# 2_cubesat_bus.net
KiCad netlist of a schematic drawn in Altium Designer
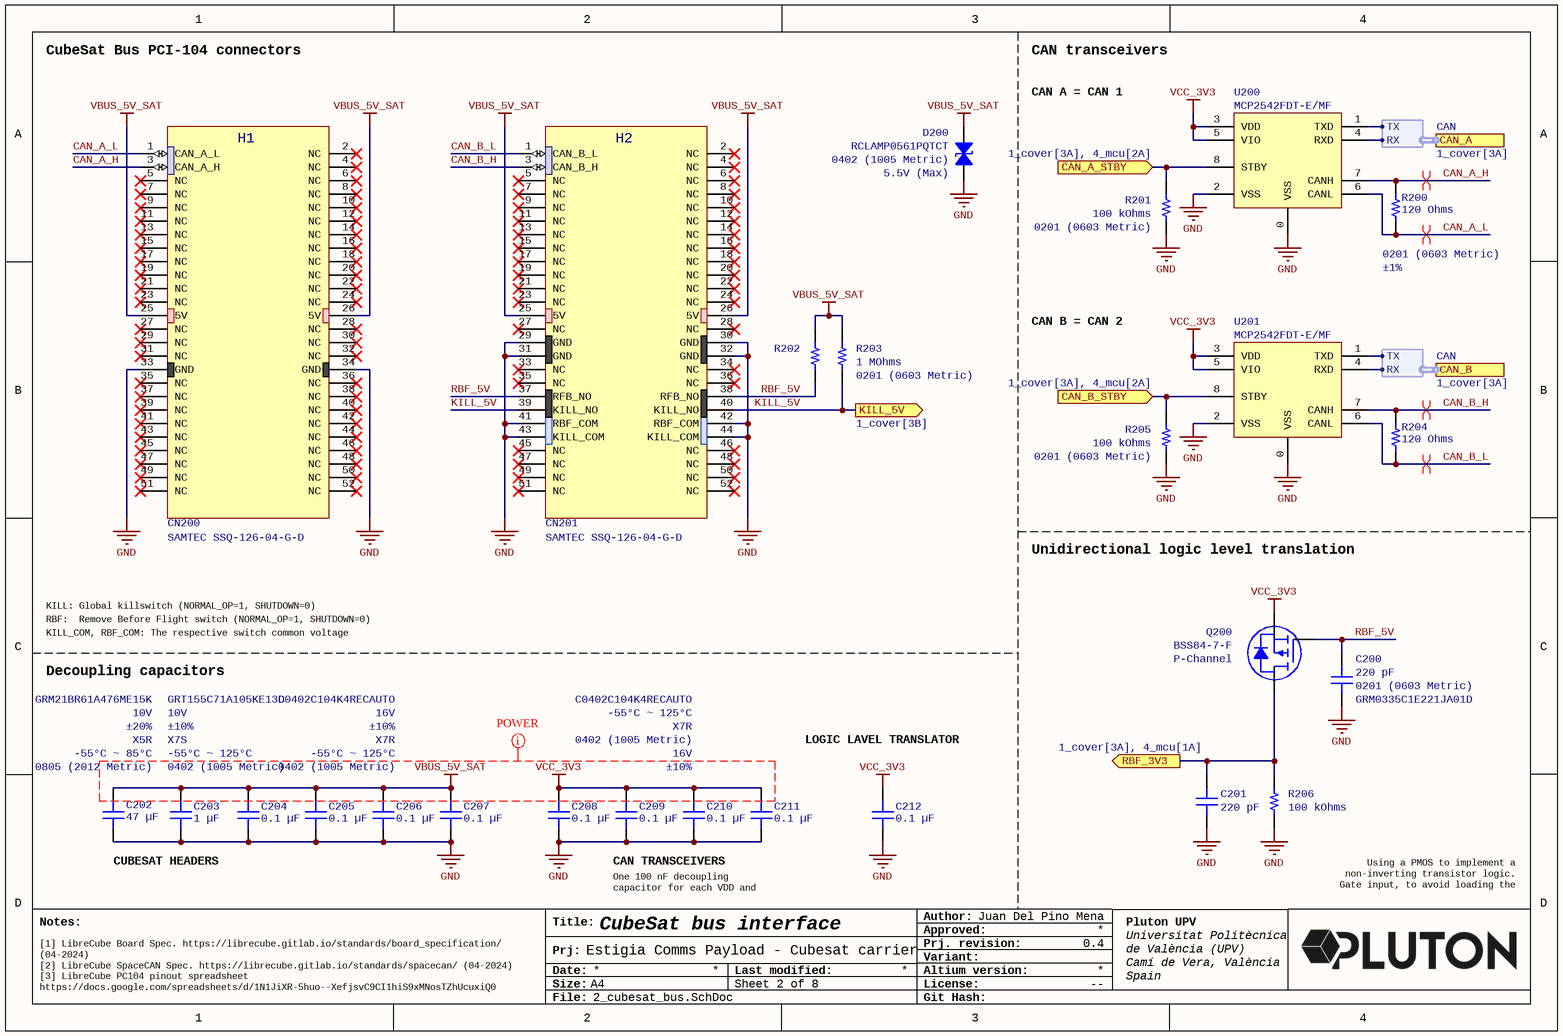
[diagram p0: 2_cubesat_bus.SchDoc]

(export (version "E")
  (design (tool "Eeschema 10.0.6"))
  (components
    (comp (ref "C200")
      (value "220 pF")
      (footprint "CAP 0201_0603")
      (description "CAP CER 220PF 25V C0G/NP0 0201")
      (fields
        (field (name "PART NUMBER") "GRM0335C1E221JA01D")
        (field (name "DEVICE PACKAGE") "0201 (0603 Metric)")
        (field (name "MANUFACTURER") "Murata Electronics")
        (field (name "TOLERANCE") "±5%")
      )
      (libsource (lib "Celestial Altium Library - altium_library") (part "Capacitor"))
    )
    (comp (ref "C201")
      (value "220 pF")
      (footprint "CAP 0201_0603")
      (description "CAP CER 220PF 25V C0G/NP0 0201")
      (fields
        (field (name "PART NUMBER") "GRM0335C1E221JA01D")
        (field (name "MANUFACTURER") "Murata Electronics")
      )
      (libsource (lib "Celestial Altium Library - altium_library") (part "Capacitor"))
    )
    (comp (ref "C202")
      (value "47 µF")
      (footprint "CAP 0805_2012")
      (description "CAP CER 47UF 10V X5R 0805")
      (fields
        (field (name "PART NUMBER") "GRM21BR61A476ME15K")
        (field (name "DEVICE PACKAGE") "0805 (2012 Metric)")
        (field (name "MANUFACTURER") "Murata Electronics")
        (field (name "OPERATING TEMPERATURE") "-55°C ~ 85°C")
        (field (name "TEMPERATURE COEFFICIENT") "X5R")
        (field (name "TOLERANCE") "±20%")
        (field (name "VOLTAGE - RATED") "10V")
      )
      (libsource (lib "Celestial Altium Library - altium_library") (part "Capacitor"))
    )
    (comp (ref "C203")
      (value "1 µF")
      (footprint "CAP 0402_1005")
      (description "CAP CER 1UF 10V X7S 0402")
      (fields
        (field (name "PART NUMBER") "GRT155C71A105KE13D")
        (field (name "DEVICE PACKAGE") "0402 (1005 Metric)")
        (field (name "MANUFACTURER") "Murata Electronics")
        (field (name "OPERATING TEMPERATURE") "-55°C ~ 125°C")
        (field (name "TEMPERATURE COEFFICIENT") "X7S")
        (field (name "TOLERANCE") "±10%")
        (field (name "VOLTAGE - RATED") "10V")
      )
      (libsource (lib "Celestial Altium Library - altium_library") (part "Capacitor"))
    )
    (comp (ref "C204")
      (value "0.1 µF")
      (footprint "CAP 0402_1005")
      (description "CAP CER 0402 0.1UF 16V X7R 10%")
      (fields
        (field (name "PART NUMBER") "C0402C104K4RECAUTO")
        (field (name "MANUFACTURER") "KEMET")
        (field (name "OPERATING TEMPERATURE") "-55°C ~ 125°C")
        (field (name "PACKAGE / CASE") "0402 (1005 Metric)")
        (field (name "TEMPERATURE COEFFICIENT") "X7R")
        (field (name "TOLERANCE") "±10%")
        (field (name "VOLTAGE - RATED") "16V")
      )
      (libsource (lib "Celestial Altium Library - altium_library") (part "Capacitor"))
    )
    (comp (ref "C205")
      (value "0.1 µF")
      (footprint "CAP 0402_1005")
      (description "CAP CER 0402 0.1UF 16V X7R 10%")
      (fields (field (name "PART NUMBER") "C0402C104K4RECAUTO") (field (name "MANUFACTURER") "KEMET"))
      (libsource (lib "Celestial Altium Library - altium_library") (part "Capacitor"))
    )
    (comp (ref "C206")
      (value "0.1 µF")
      (footprint "CAP 0402_1005")
      (description "CAP CER 0402 0.1UF 16V X7R 10%")
      (fields (field (name "PART NUMBER") "C0402C104K4RECAUTO") (field (name "MANUFACTURER") "KEMET"))
      (libsource (lib "Celestial Altium Library - altium_library") (part "Capacitor"))
    )
    (comp (ref "C207")
      (value "0.1 µF")
      (footprint "CAP 0402_1005")
      (description "CAP CER 0402 0.1UF 16V X7R 10%")
      (fields (field (name "PART NUMBER") "C0402C104K4RECAUTO") (field (name "MANUFACTURER") "KEMET"))
      (libsource (lib "Celestial Altium Library - altium_library") (part "Capacitor"))
    )
    (comp (ref "C208")
      (value "0.1 µF")
      (footprint "CAP 0402_1005")
      (description "CAP CER 0402 0.1UF 16V X7R 10%")
      (fields (field (name "PART NUMBER") "C0402C104K4RECAUTO") (field (name "MANUFACTURER") "KEMET"))
      (libsource (lib "Celestial Altium Library - altium_library") (part "Capacitor"))
    )
    (comp (ref "C209")
      (value "0.1 µF")
      (footprint "CAP 0402_1005")
      (description "CAP CER 0402 0.1UF 16V X7R 10%")
      (fields
        (field (name "PART NUMBER") "C0402C104K4RECAUTO")
        (field (name "MANUFACTURER") "KEMET")
        (field (name "OPERATING TEMPERATURE") "-55°C ~ 125°C")
        (field (name "PACKAGE / CASE") "0402 (1005 Metric)")
        (field (name "TEMPERATURE COEFFICIENT") "X7R")
        (field (name "TOLERANCE") "±10%")
        (field (name "VOLTAGE - RATED") "16V")
      )
      (libsource (lib "Celestial Altium Library - altium_library") (part "Capacitor"))
    )
    (comp (ref "C210")
      (value "0.1 µF")
      (footprint "CAP 0402_1005")
      (description "CAP CER 0402 0.1UF 16V X7R 10%")
      (fields (field (name "PART NUMBER") "C0402C104K4RECAUTO") (field (name "MANUFACTURER") "KEMET"))
      (libsource (lib "Celestial Altium Library - altium_library") (part "Capacitor"))
    )
    (comp (ref "C211")
      (value "0.1 µF")
      (footprint "CAP 0402_1005")
      (description "CAP CER 0402 0.1UF 16V X7R 10%")
      (fields (field (name "PART NUMBER") "C0402C104K4RECAUTO") (field (name "MANUFACTURER") "KEMET"))
      (libsource (lib "Celestial Altium Library - altium_library") (part "Capacitor"))
    )
    (comp (ref "C212")
      (value "0.1 µF")
      (footprint "CAP 0402_1005")
      (description "CAP CER 0402 0.1UF 16V X7R 10%")
      (fields (field (name "PART NUMBER") "C0402C104K4RECAUTO") (field (name "MANUFACTURER") "KEMET"))
      (libsource (lib "Celestial Altium Library - altium_library") (part "Capacitor"))
    )
    (comp (ref "CN200")
      (value "SAMTEC SSQ-126-04-G-D")
      (footprint "connectors:SAMTEC SSQ-126-04-G-D")
      (description "LoRa Payload only pins SAMTEC SSQ-126-04-G-D")
      (libsource (lib "cubesat_bus") (part "CubeSat Header H1 LoRa PL"))
    )
    (comp (ref "CN201")
      (value "SAMTEC SSQ-126-04-G-D")
      (footprint "connectors:SAMTEC SSQ-126-04-G-D")
      (description "LoRa Payload only pins")
      (libsource (lib "cubesat_bus") (part "CubeSat Header H2 LoRa PL"))
    )
    (comp (ref "D200")
      (value "RCLAMP0561PQTCT")
      (footprint "0402")
      (description "1-LINE 5V 0.15PF 1.1R ESD SLP100")
      (fields
        (field (name "PART NUMBER") "RCLAMP0561PQTCT")
        (field (name "DEVICE PACKAGE") "0402 (1005 Metric)")
        (field (name "MANUFACTURER") "Semtech Corporation")
        (field (name "VOLTAGE - REVERSE STANDOFF (TYP)") "5.5V (Max)")
      )
      (libsource (lib "Celestial Altium Library - altium_library") (part "Diode TVS"))
    )
    (comp (ref "Q200")
      (value "BSS84-7-F")
      (footprint "DIODES SOT-23-3")
      (description "MOSFET P-CH 50V 130MA SOT23-3")
      (fields
        (field (name "PART NUMBER") "BSS84-7-F")
        (field (name "FET TYPE") "P-Channel")
        (field (name "MANUFACTURER") "Diodes Incorporated")
      )
      (libsource (lib "Celestial Altium Library - altium_library") (part "DIODES MOSFET P-CH SOT-23-3"))
    )
    (comp (ref "R200")
      (value "120 Ohms")
      (footprint "RES 0201_0603")
      (description "RES SMD 120 OHM 1% 1/20W 0201")
      (fields
        (field (name "PART NUMBER") "CRCW0201120RFNED")
        (field (name "DEVICE PACKAGE") "0201 (0603 Metric)")
        (field (name "MANUFACTURER") "Vishay Dale")
        (field (name "TOLERANCE") "±1%")
      )
      (libsource (lib "Celestial Altium Library - altium_library") (part "Resistor"))
    )
    (comp (ref "R201")
      (value "100 kOhms")
      (footprint "RES 0201_0603")
      (description "RES 100K OHM 1% 1/20W 0201")
      (fields
        (field (name "PART NUMBER") "RC0201FR-13100KL")
        (field (name "DEVICE PACKAGE") "0201 (0603 Metric)")
        (field (name "MANUFACTURER") "Yageo")
      )
      (libsource (lib "Celestial Altium Library - altium_library") (part "Resistor"))
    )
    (comp (ref "R202")
      (value "1 MOhms")
      (footprint "RES 0201_0603")
      (description "RES SMD 1M OHM 5% 1/20W 0201")
      (fields (field (name "PART NUMBER") "CRCW02011M00JNED") (field (name "MANUFACTURER") "Vishay Dale"))
      (libsource (lib "Celestial Altium Library - altium_library") (part "Resistor"))
    )
    (comp (ref "R203")
      (value "1 MOhms")
      (footprint "RES 0201_0603")
      (description "RES SMD 1M OHM 5% 1/20W 0201")
      (fields
        (field (name "PART NUMBER") "CRCW02011M00JNED")
        (field (name "DEVICE PACKAGE") "0201 (0603 Metric)")
        (field (name "MANUFACTURER") "Vishay Dale")
      )
      (libsource (lib "Celestial Altium Library - altium_library") (part "Resistor"))
    )
    (comp (ref "R204")
      (value "120 Ohms")
      (footprint "RES 0201_0603")
      (description "RES SMD 120 OHM 1% 1/20W 0201")
      (fields (field (name "PART NUMBER") "CRCW0201120RFNED") (field (name "MANUFACTURER") "Vishay Dale"))
      (libsource (lib "Celestial Altium Library - altium_library") (part "Resistor"))
    )
    (comp (ref "R205")
      (value "100 kOhms")
      (footprint "RES 0201_0603")
      (description "RES 100K OHM 1% 1/20W 0201")
      (fields
        (field (name "PART NUMBER") "RC0201FR-13100KL")
        (field (name "DEVICE PACKAGE") "0201 (0603 Metric)")
        (field (name "MANUFACTURER") "Yageo")
      )
      (libsource (lib "Celestial Altium Library - altium_library") (part "Resistor"))
    )
    (comp (ref "R206")
      (value "100 kOhms")
      (footprint "RES 0201_0603")
      (description "RES 100K OHM 1% 1/20W 0201")
      (fields (field (name "PART NUMBER") "RC0201FR-13100KL") (field (name "MANUFACTURER") "Yageo"))
      (libsource (lib "Celestial Altium Library - altium_library") (part "Resistor"))
    )
    (comp (ref "U200")
      (value "MCP2542FDT-E/MF")
      (footprint "ics:DFN-8 3x3mm")
      (description "IC TRANSCEIVER 1/1 8DFN")
      (fields
        (field (name "MANUFACTURER") "Microchip Technology")
        (field (name "PART NUMBER") "MCP2542FDT-E/MF")
      )
      (libsource (lib "logic") (part "CAN MCP2542FDT-E/MF"))
    )
    (comp (ref "U201")
      (value "MCP2542FDT-E/MF")
      (footprint "ics:DFN-8 3x3mm")
      (description "IC TRANSCEIVER 1/1 8DFN")
      (fields
        (field (name "MANUFACTURER") "Microchip Technology")
        (field (name "PART NUMBER") "MCP2542FDT-E/MF")
      )
      (libsource (lib "logic") (part "CAN MCP2542FDT-E/MF"))
    )
  )
  (nets
    (net (code "2") (name "/CAN_A_H") (class "Default")
      (node (ref "CN200") (pin "3") (pinfunction "CAN_A_H_3") (pintype "bidirectional"))
      (node (ref "R200") (pin "2") (pinfunction "2_2") (pintype "passive"))
      (node (ref "U200") (pin "7") (pinfunction "CANH_7") (pintype "passive"))
    )
    (net (code "3") (name "/CAN_A_L") (class "Default")
      (node (ref "CN200") (pin "1") (pinfunction "CAN_A_L_1") (pintype "bidirectional"))
      (node (ref "R200") (pin "1") (pinfunction "1_1") (pintype "passive"))
      (node (ref "U200") (pin "6") (pinfunction "CANL_6") (pintype "passive"))
    )
    (net (code "4") (name "/CAN_A_STBY") (class "Default")
      (node (ref "R201") (pin "2") (pinfunction "2_2") (pintype "passive"))
      (node (ref "U200") (pin "8") (pinfunction "STBY_8") (pintype "passive"))
    )
    (net (code "5") (name "/CAN_B_H") (class "Default")
      (node (ref "CN201") (pin "3") (pinfunction "CAN_B_H_3") (pintype "bidirectional"))
      (node (ref "R204") (pin "2") (pinfunction "2_2") (pintype "passive"))
      (node (ref "U201") (pin "7") (pinfunction "CANH_7") (pintype "passive"))
    )
    (net (code "6") (name "/CAN_B_L") (class "Default")
      (node (ref "CN201") (pin "1") (pinfunction "CAN_B_L_1") (pintype "bidirectional"))
      (node (ref "R204") (pin "1") (pinfunction "1_1") (pintype "passive"))
      (node (ref "U201") (pin "6") (pinfunction "CANL_6") (pintype "passive"))
    )
    (net (code "7") (name "/CAN_B_STBY") (class "Default")
      (node (ref "R205") (pin "2") (pinfunction "2_2") (pintype "passive"))
      (node (ref "U201") (pin "8") (pinfunction "STBY_8") (pintype "passive"))
    )
    (net (code "8") (name "/KILL_5V") (class "Default")
      (node (ref "CN201") (pin "39") (pinfunction "KILL_NO_39") (pintype "passive"))
      (node (ref "CN201") (pin "40") (pinfunction "KILL_NO_40") (pintype "passive"))
      (node (ref "R203") (pin "1") (pinfunction "1_1") (pintype "passive"))
    )
    (net (code "9") (name "/RBF_3V3") (class "Default")
      (node (ref "C201") (pin "2") (pinfunction "2_2") (pintype "passive"))
      (node (ref "Q200") (pin "3") (pinfunction "D_3") (pintype "passive"))
      (node (ref "R206") (pin "1") (pinfunction "1_1") (pintype "passive"))
    )
    (net (code "10") (name "/RBF_5V") (class "Default")
      (node (ref "C200") (pin "2") (pinfunction "2_2") (pintype "passive"))
      (node (ref "CN201") (pin "37") (pinfunction "RFB_NO_37") (pintype "passive"))
      (node (ref "CN201") (pin "38") (pinfunction "RFB_NO_38") (pintype "passive"))
      (node (ref "Q200") (pin "1") (pinfunction "G_1") (pintype "passive"))
      (node (ref "R202") (pin "1") (pinfunction "1_1") (pintype "passive"))
    )
    (net (code "12") (name "GND") (class "Default")
      (node (ref "C200") (pin "1") (pinfunction "1_1") (pintype "passive"))
      (node (ref "C201") (pin "1") (pinfunction "1_1") (pintype "passive"))
      (node (ref "C202") (pin "1") (pinfunction "1_1") (pintype "passive"))
      (node (ref "C203") (pin "1") (pinfunction "1_1") (pintype "passive"))
      (node (ref "C204") (pin "1") (pinfunction "1_1") (pintype "passive"))
      (node (ref "C205") (pin "1") (pinfunction "1_1") (pintype "passive"))
      (node (ref "C206") (pin "1") (pinfunction "1_1") (pintype "passive"))
      (node (ref "C207") (pin "1") (pinfunction "1_1") (pintype "passive"))
      (node (ref "C208") (pin "1") (pinfunction "1_1") (pintype "passive"))
      (node (ref "C209") (pin "1") (pinfunction "1_1") (pintype "passive"))
      (node (ref "C210") (pin "1") (pinfunction "1_1") (pintype "passive"))
      (node (ref "C211") (pin "1") (pinfunction "1_1") (pintype "passive"))
      (node (ref "C212") (pin "1") (pinfunction "1_1") (pintype "passive"))
      (node (ref "CN200") (pin "33") (pinfunction "GND_33") (pintype "power_in"))
      (node (ref "CN200") (pin "34") (pinfunction "GND_34") (pintype "power_in"))
      (node (ref "CN201") (pin "29") (pinfunction "GND_29") (pintype "power_in"))
      (node (ref "CN201") (pin "30") (pinfunction "GND_30") (pintype "power_in"))
      (node (ref "CN201") (pin "31") (pinfunction "GND_31") (pintype "power_in"))
      (node (ref "CN201") (pin "32") (pinfunction "GND_32") (pintype "power_in"))
      (node (ref "CN201") (pin "41") (pinfunction "RBF_COM_41") (pintype "passive"))
      (node (ref "CN201") (pin "42") (pinfunction "RBF_COM_42") (pintype "passive"))
      (node (ref "CN201") (pin "43") (pinfunction "KILL_COM_43") (pintype "passive"))
      (node (ref "CN201") (pin "44") (pinfunction "KILL_COM_44") (pintype "passive"))
      (node (ref "D200") (pin "1") (pinfunction "1_1") (pintype "passive"))
      (node (ref "R201") (pin "1") (pinfunction "1_1") (pintype "passive"))
      (node (ref "R205") (pin "1") (pinfunction "1_1") (pintype "passive"))
      (node (ref "R206") (pin "2") (pinfunction "2_2") (pintype "passive"))
      (node (ref "U200") (pin "0") (pinfunction "VSS_0") (pintype "passive"))
      (node (ref "U200") (pin "2") (pinfunction "VSS_2") (pintype "passive"))
      (node (ref "U201") (pin "0") (pinfunction "VSS_0") (pintype "passive"))
      (node (ref "U201") (pin "2") (pinfunction "VSS_2") (pintype "passive"))
    )
    (net (code "13") (name "VBUS_5V_SAT") (class "Default")
      (node (ref "C202") (pin "2") (pinfunction "2_2") (pintype "passive"))
      (node (ref "C203") (pin "2") (pinfunction "2_2") (pintype "passive"))
      (node (ref "C204") (pin "2") (pinfunction "2_2") (pintype "passive"))
      (node (ref "C205") (pin "2") (pinfunction "2_2") (pintype "passive"))
      (node (ref "C206") (pin "2") (pinfunction "2_2") (pintype "passive"))
      (node (ref "C207") (pin "2") (pinfunction "2_2") (pintype "passive"))
      (node (ref "CN200") (pin "25") (pinfunction "5V_25") (pintype "power_in"))
      (node (ref "CN200") (pin "26") (pinfunction "5V_26") (pintype "power_in"))
      (node (ref "CN201") (pin "25") (pinfunction "5V_25") (pintype "power_in"))
      (node (ref "CN201") (pin "26") (pinfunction "5V_26") (pintype "power_in"))
      (node (ref "D200") (pin "2") (pinfunction "2_2") (pintype "passive"))
      (node (ref "R202") (pin "2") (pinfunction "2_2") (pintype "passive"))
      (node (ref "R203") (pin "2") (pinfunction "2_2") (pintype "passive"))
    )
    (net (code "14") (name "VCC_3V3") (class "Default")
      (node (ref "C208") (pin "2") (pinfunction "2_2") (pintype "passive"))
      (node (ref "C209") (pin "2") (pinfunction "2_2") (pintype "passive"))
      (node (ref "C210") (pin "2") (pinfunction "2_2") (pintype "passive"))
      (node (ref "C211") (pin "2") (pinfunction "2_2") (pintype "passive"))
      (node (ref "C212") (pin "2") (pinfunction "2_2") (pintype "passive"))
      (node (ref "Q200") (pin "2") (pinfunction "S_2") (pintype "passive"))
      (node (ref "U200") (pin "3") (pinfunction "VDD_3") (pintype "passive"))
      (node (ref "U200") (pin "5") (pinfunction "VIO_5") (pintype "passive"))
      (node (ref "U201") (pin "3") (pinfunction "VDD_3") (pintype "passive"))
      (node (ref "U201") (pin "5") (pinfunction "VIO_5") (pintype "passive"))
    )
    (net (code "15") (name "unconnected-(CN200-NC-Pad2)") (class "Default")
      (node (ref "CN200") (pin "2") (pinfunction "NC_2") (pintype "passive+no_connect"))
    )
    (net (code "16") (name "unconnected-(CN200-NC-Pad4)") (class "Default")
      (node (ref "CN200") (pin "4") (pinfunction "NC_4") (pintype "passive+no_connect"))
    )
    (net (code "17") (name "unconnected-(CN200-NC-Pad5)") (class "Default")
      (node (ref "CN200") (pin "5") (pinfunction "NC_5") (pintype "passive+no_connect"))
    )
    (net (code "18") (name "unconnected-(CN200-NC-Pad6)") (class "Default")
      (node (ref "CN200") (pin "6") (pinfunction "NC_6") (pintype "passive+no_connect"))
    )
    (net (code "19") (name "unconnected-(CN200-NC-Pad7)") (class "Default")
      (node (ref "CN200") (pin "7") (pinfunction "NC_7") (pintype "passive+no_connect"))
    )
    (net (code "20") (name "unconnected-(CN200-NC-Pad8)") (class "Default")
      (node (ref "CN200") (pin "8") (pinfunction "NC_8") (pintype "passive+no_connect"))
    )
    (net (code "21") (name "unconnected-(CN200-NC-Pad9)") (class "Default")
      (node (ref "CN200") (pin "9") (pinfunction "NC_9") (pintype "passive+no_connect"))
    )
    (net (code "22") (name "unconnected-(CN200-NC-Pad10)") (class "Default")
      (node (ref "CN200") (pin "10") (pinfunction "NC_10") (pintype "passive+no_connect"))
    )
    (net (code "23") (name "unconnected-(CN200-NC-Pad11)") (class "Default")
      (node (ref "CN200") (pin "11") (pinfunction "NC_11") (pintype "passive+no_connect"))
    )
    (net (code "24") (name "unconnected-(CN200-NC-Pad12)") (class "Default")
      (node (ref "CN200") (pin "12") (pinfunction "NC_12") (pintype "passive+no_connect"))
    )
    (net (code "25") (name "unconnected-(CN200-NC-Pad13)") (class "Default")
      (node (ref "CN200") (pin "13") (pinfunction "NC_13") (pintype "passive+no_connect"))
    )
    (net (code "26") (name "unconnected-(CN200-NC-Pad14)") (class "Default")
      (node (ref "CN200") (pin "14") (pinfunction "NC_14") (pintype "passive+no_connect"))
    )
    (net (code "27") (name "unconnected-(CN200-NC-Pad15)") (class "Default")
      (node (ref "CN200") (pin "15") (pinfunction "NC_15") (pintype "passive+no_connect"))
    )
    (net (code "28") (name "unconnected-(CN200-NC-Pad16)") (class "Default")
      (node (ref "CN200") (pin "16") (pinfunction "NC_16") (pintype "passive+no_connect"))
    )
    (net (code "29") (name "unconnected-(CN200-NC-Pad17)") (class "Default")
      (node (ref "CN200") (pin "17") (pinfunction "NC_17") (pintype "passive+no_connect"))
    )
    (net (code "30") (name "unconnected-(CN200-NC-Pad18)") (class "Default")
      (node (ref "CN200") (pin "18") (pinfunction "NC_18") (pintype "passive+no_connect"))
    )
    (net (code "31") (name "unconnected-(CN200-NC-Pad19)") (class "Default")
      (node (ref "CN200") (pin "19") (pinfunction "NC_19") (pintype "passive+no_connect"))
    )
    (net (code "32") (name "unconnected-(CN200-NC-Pad20)") (class "Default")
      (node (ref "CN200") (pin "20") (pinfunction "NC_20") (pintype "passive+no_connect"))
    )
    (net (code "33") (name "unconnected-(CN200-NC-Pad21)") (class "Default")
      (node (ref "CN200") (pin "21") (pinfunction "NC_21") (pintype "passive+no_connect"))
    )
    (net (code "34") (name "unconnected-(CN200-NC-Pad22)") (class "Default")
      (node (ref "CN200") (pin "22") (pinfunction "NC_22") (pintype "passive+no_connect"))
    )
    (net (code "35") (name "unconnected-(CN200-NC-Pad23)") (class "Default")
      (node (ref "CN200") (pin "23") (pinfunction "NC_23") (pintype "passive+no_connect"))
    )
    (net (code "36") (name "unconnected-(CN200-NC-Pad24)") (class "Default")
      (node (ref "CN200") (pin "24") (pinfunction "NC_24") (pintype "passive+no_connect"))
    )
    (net (code "37") (name "unconnected-(CN200-NC-Pad27)") (class "Default")
      (node (ref "CN200") (pin "27") (pinfunction "NC_27") (pintype "passive+no_connect"))
    )
    (net (code "38") (name "unconnected-(CN200-NC-Pad28)") (class "Default")
      (node (ref "CN200") (pin "28") (pinfunction "NC_28") (pintype "passive+no_connect"))
    )
    (net (code "39") (name "unconnected-(CN200-NC-Pad29)") (class "Default")
      (node (ref "CN200") (pin "29") (pinfunction "NC_29") (pintype "passive+no_connect"))
    )
    (net (code "40") (name "unconnected-(CN200-NC-Pad30)") (class "Default")
      (node (ref "CN200") (pin "30") (pinfunction "NC_30") (pintype "passive+no_connect"))
    )
    (net (code "41") (name "unconnected-(CN200-NC-Pad31)") (class "Default")
      (node (ref "CN200") (pin "31") (pinfunction "NC_31") (pintype "passive+no_connect"))
    )
    (net (code "42") (name "unconnected-(CN200-NC-Pad32)") (class "Default")
      (node (ref "CN200") (pin "32") (pinfunction "NC_32") (pintype "passive+no_connect"))
    )
    (net (code "43") (name "unconnected-(CN200-NC-Pad35)") (class "Default")
      (node (ref "CN200") (pin "35") (pinfunction "NC_35") (pintype "passive+no_connect"))
    )
    (net (code "44") (name "unconnected-(CN200-NC-Pad36)") (class "Default")
      (node (ref "CN200") (pin "36") (pinfunction "NC_36") (pintype "passive+no_connect"))
    )
    (net (code "45") (name "unconnected-(CN200-NC-Pad37)") (class "Default")
      (node (ref "CN200") (pin "37") (pinfunction "NC_37") (pintype "passive+no_connect"))
    )
    (net (code "46") (name "unconnected-(CN200-NC-Pad38)") (class "Default")
      (node (ref "CN200") (pin "38") (pinfunction "NC_38") (pintype "passive+no_connect"))
    )
    (net (code "47") (name "unconnected-(CN200-NC-Pad39)") (class "Default")
      (node (ref "CN200") (pin "39") (pinfunction "NC_39") (pintype "passive+no_connect"))
    )
    (net (code "48") (name "unconnected-(CN200-NC-Pad40)") (class "Default")
      (node (ref "CN200") (pin "40") (pinfunction "NC_40") (pintype "passive+no_connect"))
    )
    (net (code "49") (name "unconnected-(CN200-NC-Pad41)") (class "Default")
      (node (ref "CN200") (pin "41") (pinfunction "NC_41") (pintype "passive+no_connect"))
    )
    (net (code "50") (name "unconnected-(CN200-NC-Pad42)") (class "Default")
      (node (ref "CN200") (pin "42") (pinfunction "NC_42") (pintype "passive+no_connect"))
    )
    (net (code "51") (name "unconnected-(CN200-NC-Pad43)") (class "Default")
      (node (ref "CN200") (pin "43") (pinfunction "NC_43") (pintype "passive+no_connect"))
    )
    (net (code "52") (name "unconnected-(CN200-NC-Pad44)") (class "Default")
      (node (ref "CN200") (pin "44") (pinfunction "NC_44") (pintype "passive+no_connect"))
    )
    (net (code "53") (name "unconnected-(CN200-NC-Pad45)") (class "Default")
      (node (ref "CN200") (pin "45") (pinfunction "NC_45") (pintype "passive+no_connect"))
    )
    (net (code "54") (name "unconnected-(CN200-NC-Pad46)") (class "Default")
      (node (ref "CN200") (pin "46") (pinfunction "NC_46") (pintype "passive+no_connect"))
    )
    (net (code "55") (name "unconnected-(CN200-NC-Pad47)") (class "Default")
      (node (ref "CN200") (pin "47") (pinfunction "NC_47") (pintype "passive+no_connect"))
    )
    (net (code "56") (name "unconnected-(CN200-NC-Pad48)") (class "Default")
      (node (ref "CN200") (pin "48") (pinfunction "NC_48") (pintype "passive+no_connect"))
    )
    (net (code "57") (name "unconnected-(CN200-NC-Pad49)") (class "Default")
      (node (ref "CN200") (pin "49") (pinfunction "NC_49") (pintype "passive+no_connect"))
    )
    (net (code "58") (name "unconnected-(CN200-NC-Pad50)") (class "Default")
      (node (ref "CN200") (pin "50") (pinfunction "NC_50") (pintype "passive+no_connect"))
    )
    (net (code "59") (name "unconnected-(CN200-NC-Pad51)") (class "Default")
      (node (ref "CN200") (pin "51") (pinfunction "NC_51") (pintype "passive+no_connect"))
    )
    (net (code "60") (name "unconnected-(CN200-NC-Pad52)") (class "Default")
      (node (ref "CN200") (pin "52") (pinfunction "NC_52") (pintype "passive+no_connect"))
    )
    (net (code "61") (name "unconnected-(CN201-NC-Pad2)") (class "Default")
      (node (ref "CN201") (pin "2") (pinfunction "NC_2") (pintype "passive+no_connect"))
    )
    (net (code "62") (name "unconnected-(CN201-NC-Pad4)") (class "Default")
      (node (ref "CN201") (pin "4") (pinfunction "NC_4") (pintype "passive+no_connect"))
    )
    (net (code "63") (name "unconnected-(CN201-NC-Pad5)") (class "Default")
      (node (ref "CN201") (pin "5") (pinfunction "NC_5") (pintype "passive+no_connect"))
    )
    (net (code "64") (name "unconnected-(CN201-NC-Pad6)") (class "Default")
      (node (ref "CN201") (pin "6") (pinfunction "NC_6") (pintype "passive+no_connect"))
    )
    (net (code "65") (name "unconnected-(CN201-NC-Pad7)") (class "Default")
      (node (ref "CN201") (pin "7") (pinfunction "NC_7") (pintype "passive+no_connect"))
    )
    (net (code "66") (name "unconnected-(CN201-NC-Pad8)") (class "Default")
      (node (ref "CN201") (pin "8") (pinfunction "NC_8") (pintype "passive+no_connect"))
    )
    (net (code "67") (name "unconnected-(CN201-NC-Pad9)") (class "Default")
      (node (ref "CN201") (pin "9") (pinfunction "NC_9") (pintype "passive+no_connect"))
    )
    (net (code "68") (name "unconnected-(CN201-NC-Pad10)") (class "Default")
      (node (ref "CN201") (pin "10") (pinfunction "NC_10") (pintype "passive+no_connect"))
    )
    (net (code "69") (name "unconnected-(CN201-NC-Pad11)") (class "Default")
      (node (ref "CN201") (pin "11") (pinfunction "NC_11") (pintype "passive+no_connect"))
    )
    (net (code "70") (name "unconnected-(CN201-NC-Pad12)") (class "Default")
      (node (ref "CN201") (pin "12") (pinfunction "NC_12") (pintype "passive+no_connect"))
    )
    (net (code "71") (name "unconnected-(CN201-NC-Pad13)") (class "Default")
      (node (ref "CN201") (pin "13") (pinfunction "NC_13") (pintype "passive+no_connect"))
    )
    (net (code "72") (name "unconnected-(CN201-NC-Pad14)") (class "Default")
      (node (ref "CN201") (pin "14") (pinfunction "NC_14") (pintype "passive+no_connect"))
    )
    (net (code "73") (name "unconnected-(CN201-NC-Pad15)") (class "Default")
      (node (ref "CN201") (pin "15") (pinfunction "NC_15") (pintype "passive+no_connect"))
    )
    (net (code "74") (name "unconnected-(CN201-NC-Pad16)") (class "Default")
      (node (ref "CN201") (pin "16") (pinfunction "NC_16") (pintype "passive+no_connect"))
    )
    (net (code "75") (name "unconnected-(CN201-NC-Pad17)") (class "Default")
      (node (ref "CN201") (pin "17") (pinfunction "NC_17") (pintype "passive+no_connect"))
    )
    (net (code "76") (name "unconnected-(CN201-NC-Pad18)") (class "Default")
      (node (ref "CN201") (pin "18") (pinfunction "NC_18") (pintype "passive+no_connect"))
    )
    (net (code "77") (name "unconnected-(CN201-NC-Pad19)") (class "Default")
      (node (ref "CN201") (pin "19") (pinfunction "NC_19") (pintype "passive+no_connect"))
    )
    (net (code "78") (name "unconnected-(CN201-NC-Pad20)") (class "Default")
      (node (ref "CN201") (pin "20") (pinfunction "NC_20") (pintype "passive+no_connect"))
    )
    (net (code "79") (name "unconnected-(CN201-NC-Pad21)") (class "Default")
      (node (ref "CN201") (pin "21") (pinfunction "NC_21") (pintype "passive+no_connect"))
    )
    (net (code "80") (name "unconnected-(CN201-NC-Pad22)") (class "Default")
      (node (ref "CN201") (pin "22") (pinfunction "NC_22") (pintype "passive+no_connect"))
    )
    (net (code "81") (name "unconnected-(CN201-NC-Pad23)") (class "Default")
      (node (ref "CN201") (pin "23") (pinfunction "NC_23") (pintype "passive+no_connect"))
    )
    (net (code "82") (name "unconnected-(CN201-NC-Pad24)") (class "Default")
      (node (ref "CN201") (pin "24") (pinfunction "NC_24") (pintype "passive+no_connect"))
    )
    (net (code "83") (name "unconnected-(CN201-NC-Pad27)") (class "Default")
      (node (ref "CN201") (pin "27") (pinfunction "NC_27") (pintype "passive+no_connect"))
    )
    (net (code "84") (name "unconnected-(CN201-NC-Pad28)") (class "Default")
      (node (ref "CN201") (pin "28") (pinfunction "NC_28") (pintype "passive+no_connect"))
    )
    (net (code "85") (name "unconnected-(CN201-NC-Pad33)") (class "Default")
      (node (ref "CN201") (pin "33") (pinfunction "NC_33") (pintype "passive+no_connect"))
    )
    (net (code "86") (name "unconnected-(CN201-NC-Pad34)") (class "Default")
      (node (ref "CN201") (pin "34") (pinfunction "NC_34") (pintype "passive+no_connect"))
    )
    (net (code "87") (name "unconnected-(CN201-NC-Pad35)") (class "Default")
      (node (ref "CN201") (pin "35") (pinfunction "NC_35") (pintype "passive+no_connect"))
    )
    (net (code "88") (name "unconnected-(CN201-NC-Pad36)") (class "Default")
      (node (ref "CN201") (pin "36") (pinfunction "NC_36") (pintype "passive+no_connect"))
    )
    (net (code "89") (name "unconnected-(CN201-NC-Pad45)") (class "Default")
      (node (ref "CN201") (pin "45") (pinfunction "NC_45") (pintype "power_in+no_connect"))
    )
    (net (code "90") (name "unconnected-(CN201-NC-Pad46)") (class "Default")
      (node (ref "CN201") (pin "46") (pinfunction "NC_46") (pintype "power_in+no_connect"))
    )
    (net (code "91") (name "unconnected-(CN201-NC-Pad47)") (class "Default")
      (node (ref "CN201") (pin "47") (pinfunction "NC_47") (pintype "passive+no_connect"))
    )
    (net (code "92") (name "unconnected-(CN201-NC-Pad48)") (class "Default")
      (node (ref "CN201") (pin "48") (pinfunction "NC_48") (pintype "passive+no_connect"))
    )
    (net (code "93") (name "unconnected-(CN201-NC-Pad49)") (class "Default")
      (node (ref "CN201") (pin "49") (pinfunction "NC_49") (pintype "passive+no_connect"))
    )
    (net (code "94") (name "unconnected-(CN201-NC-Pad50)") (class "Default")
      (node (ref "CN201") (pin "50") (pinfunction "NC_50") (pintype "passive+no_connect"))
    )
    (net (code "95") (name "unconnected-(CN201-NC-Pad51)") (class "Default")
      (node (ref "CN201") (pin "51") (pinfunction "NC_51") (pintype "passive+no_connect"))
    )
    (net (code "96") (name "unconnected-(CN201-NC-Pad52)") (class "Default")
      (node (ref "CN201") (pin "52") (pinfunction "NC_52") (pintype "passive+no_connect"))
    )
    (net (code "97") (name "unconnected-(U200-RXD-Pad4)") (class "Default")
      (node (ref "U200") (pin "4") (pinfunction "RXD_4") (pintype "passive"))
    )
    (net (code "98") (name "unconnected-(U200-TXD-Pad1)") (class "Default")
      (node (ref "U200") (pin "1") (pinfunction "TXD_1") (pintype "passive"))
    )
    (net (code "99") (name "unconnected-(U201-RXD-Pad4)") (class "Default")
      (node (ref "U201") (pin "4") (pinfunction "RXD_4") (pintype "passive"))
    )
    (net (code "100") (name "unconnected-(U201-TXD-Pad1)") (class "Default")
      (node (ref "U201") (pin "1") (pinfunction "TXD_1") (pintype "passive"))
    )
  )
)
